# EngineLines.net
KiCad netlist of a schematic drawn in Altium Designer
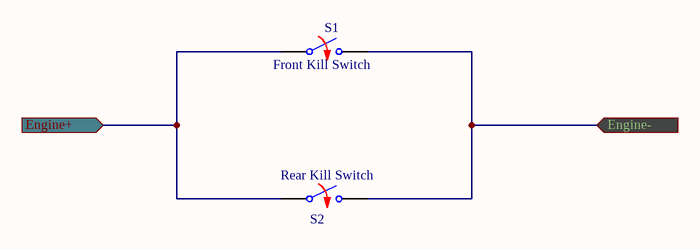
[diagram p0: EngineLines.SchDoc]

(export (version "E")
  (design (tool "Eeschema 10.0.6"))
  (components
    (comp (ref "S1")
      (value "Front Kill Switch")
      (description "Switch Normally Opened")
      (libsource (lib "Simulation Generic Components") (part "SW NO"))
    )
    (comp (ref "S2")
      (value "Rear Kill Switch")
      (description "Switch Normally Opened")
      (libsource (lib "Simulation Generic Components") (part "SW NO"))
    )
  )
  (nets
    (net (code "1") (name "/Engine+") (class "Default")
      (node (ref "S1") (pin "1") (pinfunction "1_1") (pintype "passive"))
      (node (ref "S2") (pin "1") (pinfunction "1_1") (pintype "passive"))
    )
    (net (code "2") (name "/Engine-") (class "Default")
      (node (ref "S1") (pin "2") (pinfunction "2_2") (pintype "passive"))
      (node (ref "S2") (pin "2") (pinfunction "2_2") (pintype "passive"))
    )
  )
)
